# Relay_PCB.net
KiCad netlist of a schematic drawn in Altium Designer
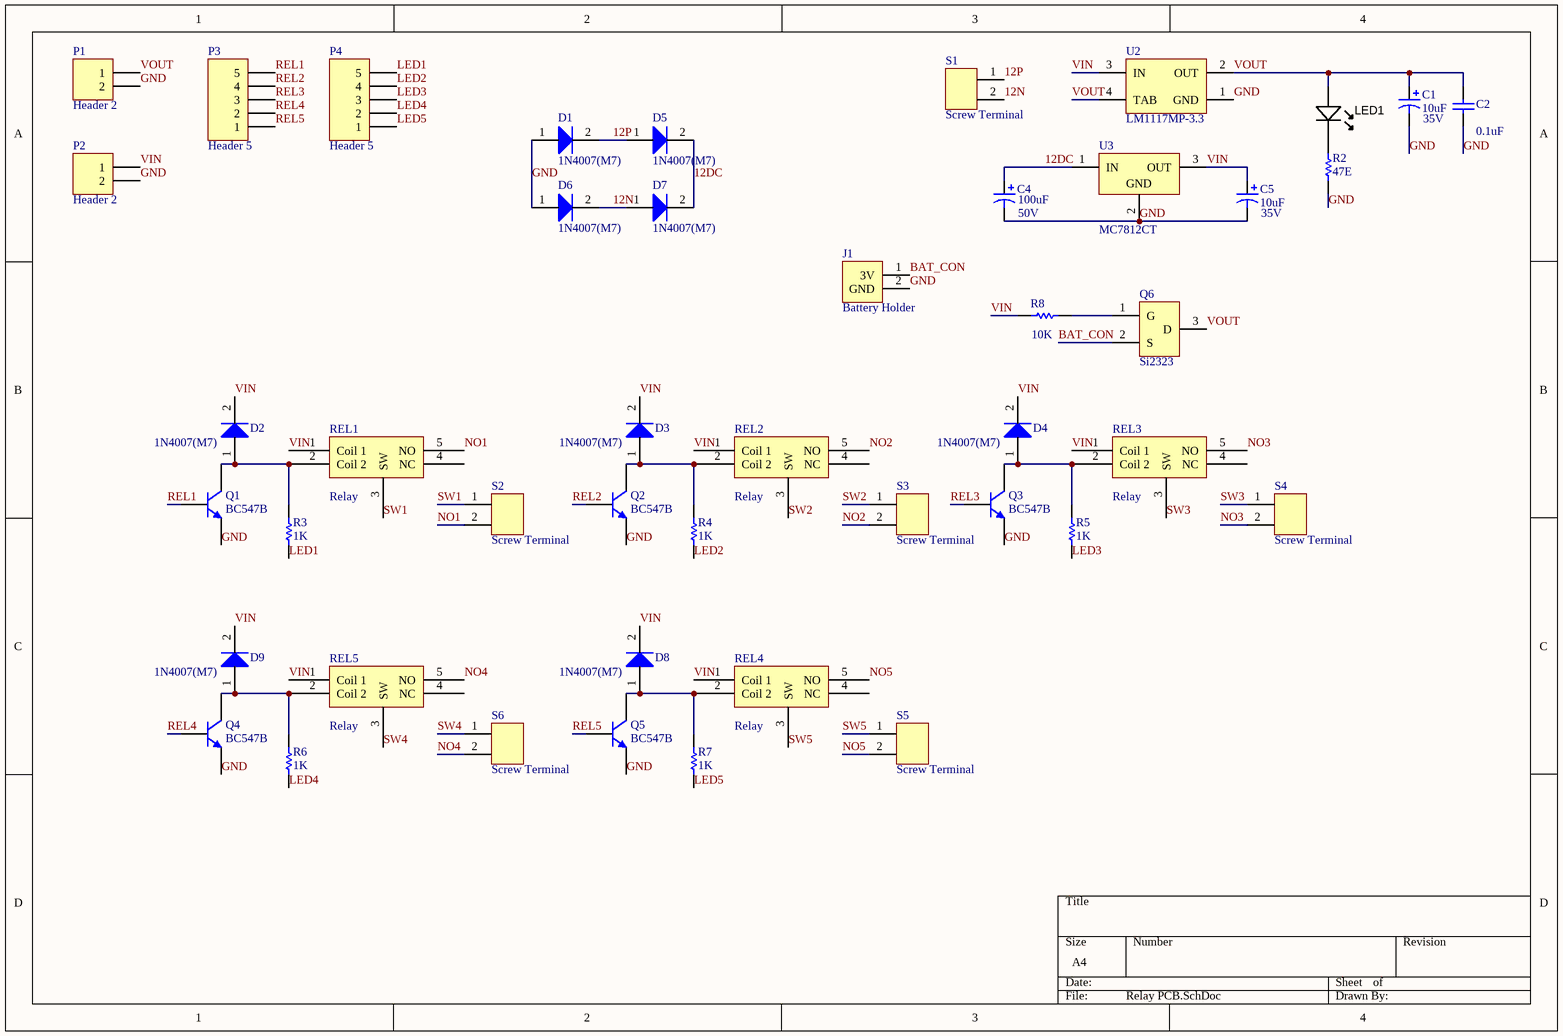
[diagram p0: Relay PCB.SchDoc]

(export (version "E")
  (design (tool "Eeschema 10.0.6"))
  (components
    (comp (ref "C1")
      (value "10uF")
      (footprint "B")
      (description "Solid Tantalum Chip Capacitor, Standard T491 Series - Industrial Grade")
      (fields (field (name "VOLTAGE") "35V") (field (name "PUBLISHER") "Altium Limited"))
      (libsource (lib "KEMET Chip Capacitor") (part "T491B"))
    )
    (comp (ref "C2")
      (value "0.1uF")
      (footprint "0805")
      (description "Ceramic Chip Capacitor - Standard")
      (fields (field (name "PUBLISHER") "Altium Limited"))
      (libsource (lib "KEMET Chip Capacitor") (part "C0805"))
    )
    (comp (ref "C4")
      (value "100uF")
      (footprint "CAPPR2-5x6.8")
      (description "Polarized Capacitor (Radial)")
      (fields
        (field (name "VOLTAGE") "50V")
        (field (name "Comment") "10uF")
        (field (name "PUBLISHER") "Altium Limited")
      )
      (libsource (lib "Miscellaneous Devices") (part "Cap Pol1"))
    )
    (comp (ref "C5")
      (value "10uF")
      (footprint "B")
      (description "Solid Tantalum Chip Capacitor, Standard T491 Series - Industrial Grade")
      (fields (field (name "VOLTAGE") "35V") (field (name "PUBLISHER") "Altium Limited"))
      (libsource (lib "KEMET Chip Capacitor") (part "T491B"))
    )
    (comp (ref "D1")
      (value "1N4007(M7)")
      (footprint "1N4007 (M7)")
      (libsource (lib "M7 Diode") (part "1N4007(M7)"))
    )
    (comp (ref "D2")
      (value "1N4007(M7)")
      (footprint "1N4007 (M7)")
      (libsource (lib "M7 Diode") (part "1N4007(M7)"))
    )
    (comp (ref "D3")
      (value "1N4007(M7)")
      (footprint "1N4007 (M7)")
      (libsource (lib "M7 Diode") (part "1N4007(M7)"))
    )
    (comp (ref "D4")
      (value "1N4007(M7)")
      (footprint "1N4007 (M7)")
      (libsource (lib "M7 Diode") (part "1N4007(M7)"))
    )
    (comp (ref "D5")
      (value "1N4007(M7)")
      (footprint "1N4007 (M7)")
      (libsource (lib "M7 Diode") (part "1N4007(M7)"))
    )
    (comp (ref "D6")
      (value "1N4007(M7)")
      (footprint "1N4007 (M7)")
      (libsource (lib "M7 Diode") (part "1N4007(M7)"))
    )
    (comp (ref "D7")
      (value "1N4007(M7)")
      (footprint "1N4007 (M7)")
      (libsource (lib "M7 Diode") (part "1N4007(M7)"))
    )
    (comp (ref "D8")
      (value "1N4007(M7)")
      (footprint "1N4007 (M7)")
      (libsource (lib "M7 Diode") (part "1N4007(M7)"))
    )
    (comp (ref "D9")
      (value "1N4007(M7)")
      (footprint "1N4007 (M7)")
      (libsource (lib "M7 Diode") (part "1N4007(M7)"))
    )
    (comp (ref "J1")
      (value "Battery Holder")
      (footprint "Battery Holder")
      (libsource (lib "Battery Holder") (part "Battery Holder"))
    )
    (comp (ref "LED1")
      (value "~")
      (footprint "LED-0805-K")
      (description "LED, 0805 SMD, Green")
      (libsource (lib "All Packages") (part "LED_SMD_Green_0805_6mcd"))
    )
    (comp (ref "P1")
      (value "Header 2")
      (footprint "HDR1X2")
      (description "Header, 2-Pin")
      (fields (field (name "PUBLISHER") "Altium Limited"))
      (libsource (lib "Miscellaneous Connectors") (part "Header 2"))
    )
    (comp (ref "P2")
      (value "Header 2")
      (footprint "HDR1X2")
      (description "Header, 2-Pin")
      (fields (field (name "PUBLISHER") "Altium Limited"))
      (libsource (lib "Miscellaneous Connectors") (part "Header 2"))
    )
    (comp (ref "P3")
      (value "Header 5")
      (footprint "HDR1X5")
      (description "Header, 5-Pin")
      (fields (field (name "PUBLISHER") "Altium Limited"))
      (libsource (lib "Miscellaneous Connectors") (part "Header 5"))
    )
    (comp (ref "P4")
      (value "Header 5")
      (footprint "HDR1X5")
      (description "Header, 5-Pin")
      (fields (field (name "PUBLISHER") "Altium Limited"))
      (libsource (lib "Miscellaneous Connectors") (part "Header 5"))
    )
    (comp (ref "Q1")
      (value "BC547B")
      (footprint "29-04")
      (description "Amplifier Transistor NPN Silicon")
      (fields (field (name "PUBLISHER") "Altium Limited"))
      (libsource (lib "Motorola Discrete BJT") (part "BC547B"))
    )
    (comp (ref "Q2")
      (value "BC547B")
      (footprint "29-04")
      (description "Amplifier Transistor NPN Silicon")
      (fields (field (name "PUBLISHER") "Altium Limited"))
      (libsource (lib "Motorola Discrete BJT") (part "BC547B"))
    )
    (comp (ref "Q3")
      (value "BC547B")
      (footprint "29-04")
      (description "Amplifier Transistor NPN Silicon")
      (fields (field (name "PUBLISHER") "Altium Limited"))
      (libsource (lib "Motorola Discrete BJT") (part "BC547B"))
    )
    (comp (ref "Q4")
      (value "BC547B")
      (footprint "29-04")
      (description "Amplifier Transistor NPN Silicon")
      (fields (field (name "PUBLISHER") "Altium Limited"))
      (libsource (lib "Motorola Discrete BJT") (part "BC547B"))
    )
    (comp (ref "Q5")
      (value "BC547B")
      (footprint "29-04")
      (description "Amplifier Transistor NPN Silicon")
      (fields (field (name "PUBLISHER") "Altium Limited"))
      (libsource (lib "Motorola Discrete BJT") (part "BC547B"))
    )
    (comp (ref "Q6") (value "Si2323") (footprint "Si2323 PMOS") (libsource (lib "Si2323") (part "Si2323")))
    (comp (ref "R2")
      (value "47E")
      (footprint "ERA-0805")
      (fields (field (name "PUBLISHER") "Altium Limited"))
      (libsource (lib "Panasonic Resistor") (part "ERA6Y"))
    )
    (comp (ref "R3")
      (value "1K")
      (footprint "ERA-0805")
      (fields (field (name "PUBLISHER") "Altium Limited"))
      (libsource (lib "Panasonic Resistor") (part "ERA6Y"))
    )
    (comp (ref "R4")
      (value "1K")
      (footprint "ERA-0805")
      (fields (field (name "PUBLISHER") "Altium Limited"))
      (libsource (lib "Panasonic Resistor") (part "ERA6Y"))
    )
    (comp (ref "R5")
      (value "1K")
      (footprint "ERA-0805")
      (fields (field (name "PUBLISHER") "Altium Limited"))
      (libsource (lib "Panasonic Resistor") (part "ERA6Y"))
    )
    (comp (ref "R6")
      (value "1K")
      (footprint "ERA-0805")
      (fields (field (name "PUBLISHER") "Altium Limited"))
      (libsource (lib "Panasonic Resistor") (part "ERA6Y"))
    )
    (comp (ref "R7")
      (value "1K")
      (footprint "ERA-0805")
      (fields (field (name "PUBLISHER") "Altium Limited"))
      (libsource (lib "Panasonic Resistor") (part "ERA6Y"))
    )
    (comp (ref "R8")
      (value "10K")
      (footprint "ERA-0805")
      (fields (field (name "PUBLISHER") "Altium Limited"))
      (libsource (lib "Panasonic Resistor") (part "ERA6Y"))
    )
    (comp (ref "REL1") (value "Relay") (footprint "Relay") (libsource (lib "Relay") (part "Relay")))
    (comp (ref "REL2") (value "Relay") (footprint "Relay") (libsource (lib "Relay") (part "Relay")))
    (comp (ref "REL3") (value "Relay") (footprint "Relay") (libsource (lib "Relay") (part "Relay")))
    (comp (ref "REL4") (value "Relay") (footprint "Relay") (libsource (lib "Relay") (part "Relay")))
    (comp (ref "REL5") (value "Relay") (footprint "Relay") (libsource (lib "Relay") (part "Relay")))
    (comp (ref "S1")
      (value "Screw Terminal")
      (footprint "Screw Terminal")
      (libsource (lib "") (part "Screw Terminal_1"))
    )
    (comp (ref "S2")
      (value "Screw Terminal")
      (footprint "Screw Terminal")
      (libsource (lib "2 Pin") (part "Screw Terminal"))
    )
    (comp (ref "S3")
      (value "Screw Terminal")
      (footprint "Screw Terminal")
      (libsource (lib "2 Pin") (part "Screw Terminal"))
    )
    (comp (ref "S4")
      (value "Screw Terminal")
      (footprint "Screw Terminal")
      (libsource (lib "2 Pin") (part "Screw Terminal"))
    )
    (comp (ref "S5")
      (value "Screw Terminal")
      (footprint "Screw Terminal")
      (libsource (lib "2 Pin") (part "Screw Terminal"))
    )
    (comp (ref "S6")
      (value "Screw Terminal")
      (footprint "Screw Terminal")
      (libsource (lib "2 Pin") (part "Screw Terminal"))
    )
    (comp (ref "U2")
      (value "LM1117MP-3.3")
      (footprint "MP04A_N")
      (description "800mA Low-Dropout Linear Regulator")
      (fields
        (field (name "MANUFACTURER") "National Semiconductor")
        (field (name "DIGIKEYPARTNUMBER") "LM1117MP-3.3CT-ND")
        (field (name "PUBLISHER") "Altium Limited")
      )
      (libsource (lib "NSC LDO") (part "LM1117MP-3.3"))
    )
    (comp (ref "U3")
      (value "MC7812CT")
      (footprint "221A-04")
      (description "3-Terminal Positive Fixed Voltage Regulator")
      (fields (field (name "PUBLISHER") "Altium Limited"))
      (libsource (lib "Motorola Power Mgt Voltage Regulator") (part "MC7812CT"))
    )
  )
  (nets
    (net (code "1") (name "/12DC") (class "Default")
      (node (ref "C4") (pin "1") (pinfunction "1_1") (pintype "passive"))
      (node (ref "D5") (pin "2") (pinfunction "K_2") (pintype "passive"))
      (node (ref "D7") (pin "2") (pinfunction "K_2") (pintype "passive"))
      (node (ref "U3") (pin "1") (pinfunction "IN_1") (pintype "power_in"))
    )
    (net (code "2") (name "/12N") (class "Default")
      (node (ref "D6") (pin "2") (pinfunction "K_2") (pintype "passive"))
      (node (ref "D7") (pin "1") (pinfunction "A_1") (pintype "passive"))
      (node (ref "S1") (pin "2") (pintype "passive"))
    )
    (net (code "3") (name "/12P") (class "Default")
      (node (ref "D1") (pin "2") (pinfunction "K_2") (pintype "passive"))
      (node (ref "D5") (pin "1") (pinfunction "A_1") (pintype "passive"))
      (node (ref "S1") (pin "1") (pintype "passive"))
    )
    (net (code "4") (name "/BAT_CON") (class "Default")
      (node (ref "J1") (pin "1") (pinfunction "3V_1") (pintype "passive"))
      (node (ref "Q6") (pin "2") (pinfunction "S_2") (pintype "passive"))
    )
    (net (code "5") (name "/GND") (class "Default")
      (node (ref "C1") (pin "2") (pinfunction "2_2") (pintype "passive"))
      (node (ref "C2") (pin "1") (pinfunction "1_1") (pintype "passive"))
      (node (ref "C4") (pin "2") (pinfunction "2_2") (pintype "passive"))
      (node (ref "C5") (pin "2") (pinfunction "2_2") (pintype "passive"))
      (node (ref "D1") (pin "1") (pinfunction "A_1") (pintype "passive"))
      (node (ref "D6") (pin "1") (pinfunction "A_1") (pintype "passive"))
      (node (ref "J1") (pin "2") (pinfunction "GND_2") (pintype "passive"))
      (node (ref "P1") (pin "2") (pinfunction "2_2") (pintype "passive"))
      (node (ref "P2") (pin "2") (pinfunction "2_2") (pintype "passive"))
      (node (ref "Q1") (pin "3") (pinfunction "E_3") (pintype "passive"))
      (node (ref "Q2") (pin "3") (pinfunction "E_3") (pintype "passive"))
      (node (ref "Q3") (pin "3") (pinfunction "E_3") (pintype "passive"))
      (node (ref "Q4") (pin "3") (pinfunction "E_3") (pintype "passive"))
      (node (ref "Q5") (pin "3") (pinfunction "E_3") (pintype "passive"))
      (node (ref "R2") (pin "2") (pinfunction "2_2") (pintype "passive"))
      (node (ref "U2") (pin "1") (pinfunction "GND_1") (pintype "power_in"))
      (node (ref "U3") (pin "2") (pinfunction "GND_2") (pintype "power_in"))
    )
    (net (code "6") (name "/LED1") (class "Default")
      (node (ref "P4") (pin "5") (pinfunction "5_5") (pintype "passive"))
      (node (ref "R3") (pin "1") (pinfunction "1_1") (pintype "passive"))
    )
    (net (code "7") (name "/LED2") (class "Default")
      (node (ref "P4") (pin "4") (pinfunction "4_4") (pintype "passive"))
      (node (ref "R4") (pin "1") (pinfunction "1_1") (pintype "passive"))
    )
    (net (code "8") (name "/LED3") (class "Default")
      (node (ref "P4") (pin "3") (pinfunction "3_3") (pintype "passive"))
      (node (ref "R5") (pin "1") (pinfunction "1_1") (pintype "passive"))
    )
    (net (code "9") (name "/LED4") (class "Default")
      (node (ref "P4") (pin "2") (pinfunction "2_2") (pintype "passive"))
      (node (ref "R6") (pin "1") (pinfunction "1_1") (pintype "passive"))
    )
    (net (code "10") (name "/LED5") (class "Default")
      (node (ref "P4") (pin "1") (pinfunction "1_1") (pintype "passive"))
      (node (ref "R7") (pin "1") (pinfunction "1_1") (pintype "passive"))
    )
    (net (code "11") (name "/NO1") (class "Default")
      (node (ref "REL1") (pin "5") (pinfunction "NO_5") (pintype "passive"))
      (node (ref "S2") (pin "2") (pintype "passive"))
    )
    (net (code "12") (name "/NO2") (class "Default")
      (node (ref "REL2") (pin "5") (pinfunction "NO_5") (pintype "passive"))
      (node (ref "S3") (pin "2") (pintype "passive"))
    )
    (net (code "13") (name "/NO3") (class "Default")
      (node (ref "REL3") (pin "5") (pinfunction "NO_5") (pintype "passive"))
      (node (ref "S4") (pin "2") (pintype "passive"))
    )
    (net (code "14") (name "/NO4") (class "Default")
      (node (ref "REL5") (pin "5") (pinfunction "NO_5") (pintype "passive"))
      (node (ref "S6") (pin "2") (pintype "passive"))
    )
    (net (code "15") (name "/NO5") (class "Default")
      (node (ref "REL4") (pin "5") (pinfunction "NO_5") (pintype "passive"))
      (node (ref "S5") (pin "2") (pintype "passive"))
    )
    (net (code "16") (name "/REL1") (class "Default")
      (node (ref "P3") (pin "5") (pinfunction "5_5") (pintype "passive"))
      (node (ref "Q1") (pin "2") (pinfunction "B_2") (pintype "passive"))
    )
    (net (code "17") (name "/REL2") (class "Default")
      (node (ref "P3") (pin "4") (pinfunction "4_4") (pintype "passive"))
      (node (ref "Q2") (pin "2") (pinfunction "B_2") (pintype "passive"))
    )
    (net (code "18") (name "/REL3") (class "Default")
      (node (ref "P3") (pin "3") (pinfunction "3_3") (pintype "passive"))
      (node (ref "Q3") (pin "2") (pinfunction "B_2") (pintype "passive"))
    )
    (net (code "19") (name "/REL4") (class "Default")
      (node (ref "P3") (pin "2") (pinfunction "2_2") (pintype "passive"))
      (node (ref "Q4") (pin "2") (pinfunction "B_2") (pintype "passive"))
    )
    (net (code "20") (name "/REL5") (class "Default")
      (node (ref "P3") (pin "1") (pinfunction "1_1") (pintype "passive"))
      (node (ref "Q5") (pin "2") (pinfunction "B_2") (pintype "passive"))
    )
    (net (code "21") (name "/SW1") (class "Default")
      (node (ref "REL1") (pin "3") (pinfunction "SW_3") (pintype "passive"))
      (node (ref "S2") (pin "1") (pintype "passive"))
    )
    (net (code "22") (name "/SW2") (class "Default")
      (node (ref "REL2") (pin "3") (pinfunction "SW_3") (pintype "passive"))
      (node (ref "S3") (pin "1") (pintype "passive"))
    )
    (net (code "23") (name "/SW3") (class "Default")
      (node (ref "REL3") (pin "3") (pinfunction "SW_3") (pintype "passive"))
      (node (ref "S4") (pin "1") (pintype "passive"))
    )
    (net (code "24") (name "/SW4") (class "Default")
      (node (ref "REL5") (pin "3") (pinfunction "SW_3") (pintype "passive"))
      (node (ref "S6") (pin "1") (pintype "passive"))
    )
    (net (code "25") (name "/SW5") (class "Default")
      (node (ref "REL4") (pin "3") (pinfunction "SW_3") (pintype "passive"))
      (node (ref "S5") (pin "1") (pintype "passive"))
    )
    (net (code "26") (name "/VIN") (class "Default")
      (node (ref "C5") (pin "1") (pinfunction "1_1") (pintype "passive"))
      (node (ref "D2") (pin "2") (pinfunction "K_2") (pintype "passive"))
      (node (ref "D3") (pin "2") (pinfunction "K_2") (pintype "passive"))
      (node (ref "D4") (pin "2") (pinfunction "K_2") (pintype "passive"))
      (node (ref "D8") (pin "2") (pinfunction "K_2") (pintype "passive"))
      (node (ref "D9") (pin "2") (pinfunction "K_2") (pintype "passive"))
      (node (ref "P2") (pin "1") (pinfunction "1_1") (pintype "passive"))
      (node (ref "R8") (pin "1") (pinfunction "1_1") (pintype "passive"))
      (node (ref "REL1") (pin "1") (pinfunction "Coil_1_1") (pintype "passive"))
      (node (ref "REL2") (pin "1") (pinfunction "Coil_1_1") (pintype "passive"))
      (node (ref "REL3") (pin "1") (pinfunction "Coil_1_1") (pintype "passive"))
      (node (ref "REL4") (pin "1") (pinfunction "Coil_1_1") (pintype "passive"))
      (node (ref "REL5") (pin "1") (pinfunction "Coil_1_1") (pintype "passive"))
      (node (ref "U2") (pin "3") (pinfunction "IN_3") (pintype "power_in"))
      (node (ref "U3") (pin "3") (pinfunction "OUT_3") (pintype "power_in"))
    )
    (net (code "27") (name "/VOUT") (class "Default")
      (node (ref "C1") (pin "1") (pinfunction "1_1") (pintype "passive"))
      (node (ref "C2") (pin "2") (pinfunction "2_2") (pintype "passive"))
      (node (ref "LED1") (pin "A") (pinfunction "A_A") (pintype "passive"))
      (node (ref "P1") (pin "1") (pinfunction "1_1") (pintype "passive"))
      (node (ref "Q6") (pin "3") (pinfunction "D_3") (pintype "passive"))
      (node (ref "U2") (pin "2") (pinfunction "OUT_2") (pintype "power_in"))
      (node (ref "U2") (pin "4") (pinfunction "TAB_4") (pintype "power_in"))
    )
    (net (code "28") (name "Net-(D2-A)") (class "Default")
      (node (ref "D2") (pin "1") (pinfunction "A_1") (pintype "passive"))
      (node (ref "Q1") (pin "1") (pinfunction "C_1") (pintype "passive"))
      (node (ref "R3") (pin "2") (pinfunction "2_2") (pintype "passive"))
      (node (ref "REL1") (pin "2") (pinfunction "Coil_2_2") (pintype "passive"))
    )
    (net (code "29") (name "Net-(D3-A)") (class "Default")
      (node (ref "D3") (pin "1") (pinfunction "A_1") (pintype "passive"))
      (node (ref "Q2") (pin "1") (pinfunction "C_1") (pintype "passive"))
      (node (ref "R4") (pin "2") (pinfunction "2_2") (pintype "passive"))
      (node (ref "REL2") (pin "2") (pinfunction "Coil_2_2") (pintype "passive"))
    )
    (net (code "30") (name "Net-(D4-A)") (class "Default")
      (node (ref "D4") (pin "1") (pinfunction "A_1") (pintype "passive"))
      (node (ref "Q3") (pin "1") (pinfunction "C_1") (pintype "passive"))
      (node (ref "R5") (pin "2") (pinfunction "2_2") (pintype "passive"))
      (node (ref "REL3") (pin "2") (pinfunction "Coil_2_2") (pintype "passive"))
    )
    (net (code "31") (name "Net-(D8-A)") (class "Default")
      (node (ref "D8") (pin "1") (pinfunction "A_1") (pintype "passive"))
      (node (ref "Q5") (pin "1") (pinfunction "C_1") (pintype "passive"))
      (node (ref "R7") (pin "2") (pinfunction "2_2") (pintype "passive"))
      (node (ref "REL4") (pin "2") (pinfunction "Coil_2_2") (pintype "passive"))
    )
    (net (code "32") (name "Net-(D9-A)") (class "Default")
      (node (ref "D9") (pin "1") (pinfunction "A_1") (pintype "passive"))
      (node (ref "Q4") (pin "1") (pinfunction "C_1") (pintype "passive"))
      (node (ref "R6") (pin "2") (pinfunction "2_2") (pintype "passive"))
      (node (ref "REL5") (pin "2") (pinfunction "Coil_2_2") (pintype "passive"))
    )
    (net (code "33") (name "Net-(LED1-PadK)") (class "Default")
      (node (ref "LED1") (pin "K") (pinfunction "K_K") (pintype "passive"))
      (node (ref "R2") (pin "1") (pinfunction "1_1") (pintype "passive"))
    )
    (net (code "34") (name "Net-(Q6-G)") (class "Default")
      (node (ref "Q6") (pin "1") (pinfunction "G_1") (pintype "passive"))
      (node (ref "R8") (pin "2") (pinfunction "2_2") (pintype "passive"))
    )
    (net (code "35") (name "unconnected-(REL1-NC-Pad4)") (class "Default")
      (node (ref "REL1") (pin "4") (pinfunction "NC_4") (pintype "passive"))
    )
    (net (code "36") (name "unconnected-(REL2-NC-Pad4)") (class "Default")
      (node (ref "REL2") (pin "4") (pinfunction "NC_4") (pintype "passive"))
    )
    (net (code "37") (name "unconnected-(REL3-NC-Pad4)") (class "Default")
      (node (ref "REL3") (pin "4") (pinfunction "NC_4") (pintype "passive"))
    )
    (net (code "38") (name "unconnected-(REL4-NC-Pad4)") (class "Default")
      (node (ref "REL4") (pin "4") (pinfunction "NC_4") (pintype "passive"))
    )
    (net (code "39") (name "unconnected-(REL5-NC-Pad4)") (class "Default")
      (node (ref "REL5") (pin "4") (pinfunction "NC_4") (pintype "passive"))
    )
  )
)
